# SCHEMATIC.net
KiCad netlist of a schematic drawn in Altium Designer
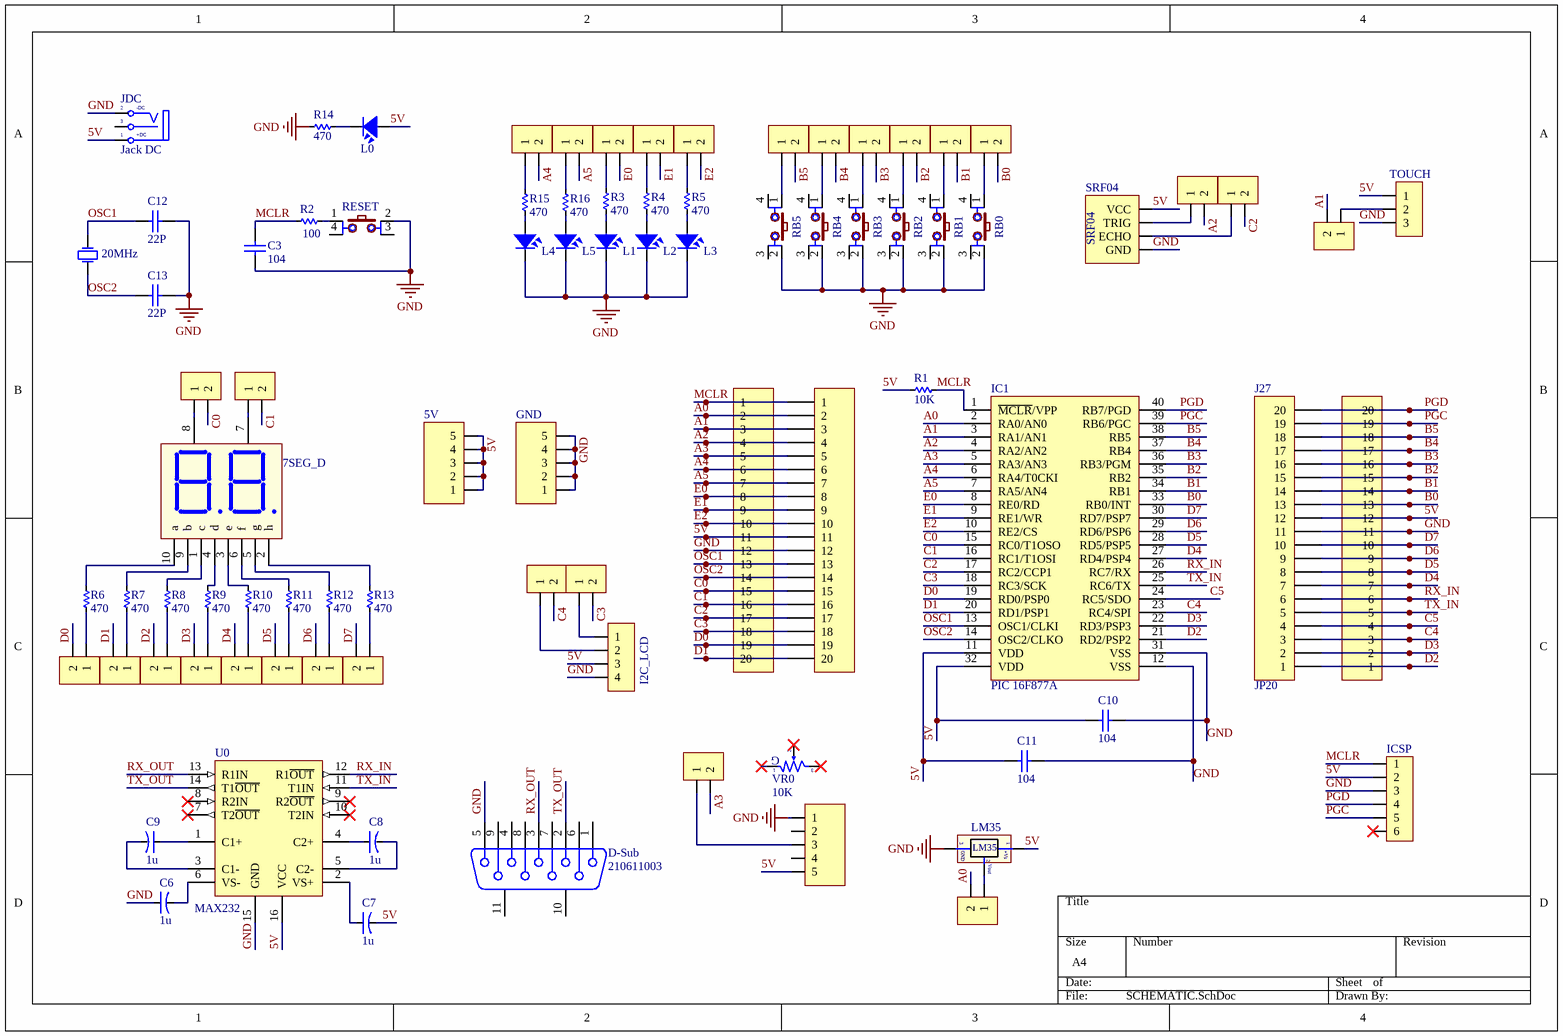
[diagram p0: SCHEMATIC.SchDoc]

(export (version "E")
  (design (tool "Eeschema 10.0.6"))
  (components
    (comp (ref "5V")
      (value "JP5")
      (footprint "JP5-C1T")
      (description "WR-PHD 2.54 mm Angled Socket Header")
      (fields
        (field (name "MANUFACTURER") "Würth Elektronik eiSos GmbH")
        (field (name "PARTNO") "613005143121")
        (field (name "CREATED BY") "Karrer Zheng")
      )
      (libsource (lib "") (part "JP5_1"))
    )
    (comp (ref "C3")
      (value "104")
      (footprint "CN1.5")
      (description "Capacitor")
      (fields (field (name "Comment") "Cap Non-Pol"))
      (libsource (lib "TechMT.VN_Lib_Project v1.0") (part "Cap Non-Pol"))
    )
    (comp (ref "C6")
      (value "1u")
      (footprint "CA-ALU-2.54")
      (description "Capacitor (Semiconductor SIM Model)")
      (fields (field (name "PUBLISHER") "Altium Limited"))
      (libsource (lib "THU VIEN DAY DU") (part "CN-ALU-DIP"))
    )
    (comp (ref "C7")
      (value "1u")
      (footprint "CA-ALU-2.54")
      (description "Capacitor (Semiconductor SIM Model)")
      (fields (field (name "PUBLISHER") "Altium Limited"))
      (libsource (lib "THU VIEN DAY DU") (part "CN-ALU-DIP"))
    )
    (comp (ref "C8")
      (value "1u")
      (footprint "CA-ALU-2.54")
      (description "Capacitor (Semiconductor SIM Model)")
      (fields (field (name "PUBLISHER") "Altium Limited"))
      (libsource (lib "THU VIEN DAY DU") (part "CN-ALU-DIP"))
    )
    (comp (ref "C9")
      (value "1u")
      (footprint "CA-ALU-2.54")
      (description "Capacitor (Semiconductor SIM Model)")
      (fields (field (name "PUBLISHER") "Altium Limited"))
      (libsource (lib "THU VIEN DAY DU") (part "CN-ALU-DIP"))
    )
    (comp (ref "C10")
      (value "104")
      (footprint "CN1.5")
      (description "Capacitor")
      (fields (field (name "Comment") "Cap Non-Pol"))
      (libsource (lib "TechMT.VN_Lib_Project v1.0") (part "Cap Non-Pol"))
    )
    (comp (ref "C11")
      (value "104")
      (footprint "CN1.5")
      (description "Capacitor")
      (fields (field (name "Comment") "Cap Non-Pol"))
      (libsource (lib "TechMT.VN_Lib_Project v1.0") (part "Cap Non-Pol"))
    )
    (comp (ref "C12")
      (value "22P")
      (footprint "CN1.5")
      (description "Capacitor")
      (fields (field (name "Comment") "Cap Non-Pol"))
      (libsource (lib "TechMT.VN_Lib_Project v1.0") (part "Cap Non-Pol"))
    )
    (comp (ref "C13")
      (value "22P")
      (footprint "CN1.5")
      (description "Capacitor")
      (fields (field (name "Comment") "Cap Non-Pol"))
      (libsource (lib "TechMT.VN_Lib_Project v1.0") (part "Cap Non-Pol"))
    )
    (comp (ref "D-Sub")
      (value "210611003")
      (footprint "COM9B")
      (description "D-SUB-Filter Connectors WE-DS, Solder Pin Straight")
      (fields
        (field (name "MANUFACTURER") "Würth Elektronik eiSos GmbH")
        (field (name "CREATED BY") "Christin Zierenner")
      )
      (libsource (lib "THU VIEN DAY DU") (part "CON 9BD"))
    )
    (comp (ref "DS0")
      (value "7SEG_D")
      (footprint "7SEG-D")
      (description "Dual 7 Seg Dipslay")
      (libsource (lib "TechMT.VN_Lib_Project v1.0") (part "LED7-D"))
    )
    (comp (ref "GND")
      (value "JP5")
      (footprint "JP5-C1T")
      (description "WR-PHD 2.54 mm Angled Socket Header")
      (fields
        (field (name "MANUFACTURER") "Würth Elektronik eiSos GmbH")
        (field (name "PARTNO") "613005143121")
        (field (name "CREATED BY") "Karrer Zheng")
      )
      (libsource (lib "") (part "JP5_1"))
    )
    (comp (ref "I2C_LCD")
      (value "JP4")
      (footprint "JP4-C1T")
      (description "WR-PHD 2.54 mm Angled Socket Header")
      (fields
        (field (name "MANUFACTURER") "Würth Elektronik eiSos GmbH")
        (field (name "PARTNO") "613004143121")
        (field (name "CREATED BY") "Karrer Zheng")
      )
      (libsource (lib "THU VIEN DAY DU") (part "JP4"))
    )
    (comp (ref "IC1")
      (value "PIC 16F877A")
      (footprint "DIP40_Socket")
      (description "8K FLASH, 368B RAM, 256B EFROM")
      (fields (field (name "COPYRIGHT BY") "VanDungEvn"))
      (libsource (lib "THU VIEN DAY DU") (part "PIC16F877-PU"))
    )
    (comp (ref "ICSP")
      (value "Header6")
      (footprint "Header6")
      (description "Header IDC, 6 x 1 Pin Vertical 2.54mm Pitch (Non-Boxed, Male)")
      (fields
        (field (name "MANUFACTURER") "Würth Elektronik eiSos GmbH")
        (field (name "PARTNO") "613002143121")
        (field (name "CREATED BY") "Karrer Zheng")
      )
      (libsource (lib "THU VIEN DAY DU") (part "Header6"))
    )
    (comp (ref "J0")
      (value "JP20")
      (footprint "JP20-C1T")
      (description "WR-PHD 2.54 mm Angled Socket Header")
      (fields
        (field (name "MANUFACTURER") "Würth Elektronik eiSos GmbH")
        (field (name "PARTNO") "613020143121")
        (field (name "CREATED BY") "Karrer Zheng")
      )
      (libsource (lib "") (part "JP20_1"))
    )
    (comp (ref "J2")
      (value "JP20")
      (footprint "JP20-D1T")
      (description "WR-PHD 2.54 mm Angled Socket Header")
      (fields
        (field (name "MANUFACTURER") "Würth Elektronik eiSos GmbH")
        (field (name "PARTNO") "613020143121")
        (field (name "CREATED BY") "Karrer Zheng")
      )
      (libsource (lib "THU VIEN DAY DU") (part "JP20"))
    )
    (comp (ref "J26")
      (value "JP20")
      (footprint "JP20-C1T")
      (description "WR-PHD 2.54 mm Angled Socket Header")
      (fields
        (field (name "MANUFACTURER") "Würth Elektronik eiSos GmbH")
        (field (name "PARTNO") "613020143121")
        (field (name "CREATED BY") "Karrer Zheng")
      )
      (libsource (lib "THU VIEN DAY DU") (part "JP20"))
    )
    (comp (ref "J27")
      (value "JP20")
      (footprint "JP20-D1T")
      (description "WR-PHD 2.54 mm Angled Socket Header")
      (fields
        (field (name "MANUFACTURER") "Würth Elektronik eiSos GmbH")
        (field (name "PARTNO") "613020143121")
        (field (name "CREATED BY") "Karrer Zheng")
      )
      (libsource (lib "") (part "JP20_1"))
    )
    (comp (ref "J28")
      (value "JP5")
      (footprint "JP5-C1T")
      (description "WR-PHD 2.54 mm Angled Socket Header")
      (fields
        (field (name "MANUFACTURER") "Würth Elektronik eiSos GmbH")
        (field (name "PARTNO") "613005143121")
        (field (name "CREATED BY") "Karrer Zheng")
      )
      (libsource (lib "THU VIEN DAY DU") (part "JP5"))
    )
    (comp (ref "J29")
      (value "JP2")
      (footprint "JP2-D1T")
      (description "WR-PHD 2.54 mm Angled Socket Header")
      (fields
        (field (name "MANUFACTURER") "Würth Elektronik eiSos GmbH")
        (field (name "PARTNO") "613002143121")
        (field (name "CREATED BY") "Karrer Zheng")
      )
      (libsource (lib "") (part "JP2_1"))
    )
    (comp (ref "JDC")
      (value "Jack DC")
      (footprint "DC0")
      (description "Jac DC input")
      (libsource (lib "THU VIEN DAY DU") (part "DCIN"))
    )
    (comp (ref "JP0")
      (value "JP2")
      (footprint "JP2-D1T")
      (description "WR-PHD 2.54 mm Angled Socket Header")
      (fields
        (field (name "MANUFACTURER") "Würth Elektronik eiSos GmbH")
        (field (name "PARTNO") "613002143121")
        (field (name "CREATED BY") "Karrer Zheng")
      )
      (libsource (lib "") (part "JP2_1"))
    )
    (comp (ref "JP1")
      (value "JP2")
      (footprint "JP2-D1T")
      (description "WR-PHD 2.54 mm Angled Socket Header")
      (fields
        (field (name "MANUFACTURER") "Würth Elektronik eiSos GmbH")
        (field (name "PARTNO") "613002143121")
        (field (name "CREATED BY") "Karrer Zheng")
      )
      (libsource (lib "") (part "JP2_1"))
    )
    (comp (ref "JP2")
      (value "JP2")
      (footprint "JP2-D1T")
      (description "WR-PHD 2.54 mm Angled Socket Header")
      (fields
        (field (name "MANUFACTURER") "Würth Elektronik eiSos GmbH")
        (field (name "PARTNO") "613002143121")
        (field (name "CREATED BY") "Karrer Zheng")
      )
      (libsource (lib "") (part "JP2_1"))
    )
    (comp (ref "JP3")
      (value "JP2")
      (footprint "JP2-D1T")
      (description "WR-PHD 2.54 mm Angled Socket Header")
      (fields
        (field (name "MANUFACTURER") "Würth Elektronik eiSos GmbH")
        (field (name "PARTNO") "613002143121")
        (field (name "CREATED BY") "Karrer Zheng")
      )
      (libsource (lib "") (part "JP2_1"))
    )
    (comp (ref "JP4")
      (value "JP2")
      (footprint "JP2-D1T")
      (description "WR-PHD 2.54 mm Angled Socket Header")
      (fields
        (field (name "MANUFACTURER") "Würth Elektronik eiSos GmbH")
        (field (name "PARTNO") "613002143121")
        (field (name "CREATED BY") "Karrer Zheng")
      )
      (libsource (lib "") (part "JP2_1"))
    )
    (comp (ref "JP5")
      (value "JP2")
      (footprint "JP2-D1T")
      (description "WR-PHD 2.54 mm Angled Socket Header")
      (fields
        (field (name "MANUFACTURER") "Würth Elektronik eiSos GmbH")
        (field (name "PARTNO") "613002143121")
        (field (name "CREATED BY") "Karrer Zheng")
      )
      (libsource (lib "") (part "JP2_1"))
    )
    (comp (ref "JP6")
      (value "JP2")
      (footprint "JP2-D1T")
      (description "WR-PHD 2.54 mm Angled Socket Header")
      (fields
        (field (name "MANUFACTURER") "Würth Elektronik eiSos GmbH")
        (field (name "PARTNO") "613002143121")
        (field (name "CREATED BY") "Karrer Zheng")
      )
      (libsource (lib "") (part "JP2_1"))
    )
    (comp (ref "JP7")
      (value "JP2")
      (footprint "JP2-D1T")
      (description "WR-PHD 2.54 mm Angled Socket Header")
      (fields
        (field (name "MANUFACTURER") "Würth Elektronik eiSos GmbH")
        (field (name "PARTNO") "613002143121")
        (field (name "CREATED BY") "Karrer Zheng")
      )
      (libsource (lib "") (part "JP2_1"))
    )
    (comp (ref "JP8")
      (value "JP2")
      (footprint "JP2-D1T")
      (description "WR-PHD 2.54 mm Angled Socket Header")
      (fields
        (field (name "MANUFACTURER") "Würth Elektronik eiSos GmbH")
        (field (name "PARTNO") "613002143121")
        (field (name "CREATED BY") "Karrer Zheng")
      )
      (libsource (lib "") (part "JP2_1"))
    )
    (comp (ref "JP9")
      (value "JP2")
      (footprint "JP2-D1T")
      (description "WR-PHD 2.54 mm Angled Socket Header")
      (fields
        (field (name "MANUFACTURER") "Würth Elektronik eiSos GmbH")
        (field (name "PARTNO") "613002143121")
        (field (name "CREATED BY") "Karrer Zheng")
      )
      (libsource (lib "") (part "JP2_1"))
    )
    (comp (ref "JP10")
      (value "JP2")
      (footprint "JP2-D1T")
      (description "WR-PHD 2.54 mm Angled Socket Header")
      (fields
        (field (name "MANUFACTURER") "Würth Elektronik eiSos GmbH")
        (field (name "PARTNO") "613002143121")
        (field (name "CREATED BY") "Karrer Zheng")
      )
      (libsource (lib "") (part "JP2_1"))
    )
    (comp (ref "JP11")
      (value "JP2")
      (footprint "JP2-D1T")
      (description "WR-PHD 2.54 mm Angled Socket Header")
      (fields
        (field (name "MANUFACTURER") "Würth Elektronik eiSos GmbH")
        (field (name "PARTNO") "613002143121")
        (field (name "CREATED BY") "Karrer Zheng")
      )
      (libsource (lib "THU VIEN DAY DU") (part "JP2"))
    )
    (comp (ref "JP12")
      (value "JP2")
      (footprint "JP2-D1T")
      (description "WR-PHD 2.54 mm Angled Socket Header")
      (fields
        (field (name "MANUFACTURER") "Würth Elektronik eiSos GmbH")
        (field (name "PARTNO") "613002143121")
        (field (name "CREATED BY") "Karrer Zheng")
      )
      (libsource (lib "") (part "JP2_1"))
    )
    (comp (ref "JP13")
      (value "JP2")
      (footprint "JP2-D1T")
      (description "WR-PHD 2.54 mm Angled Socket Header")
      (fields
        (field (name "MANUFACTURER") "Würth Elektronik eiSos GmbH")
        (field (name "PARTNO") "613002143121")
        (field (name "CREATED BY") "Karrer Zheng")
      )
      (libsource (lib "") (part "JP2_1"))
    )
    (comp (ref "JP14")
      (value "JP2")
      (footprint "JP2-D1T")
      (description "WR-PHD 2.54 mm Angled Socket Header")
      (fields
        (field (name "MANUFACTURER") "Würth Elektronik eiSos GmbH")
        (field (name "PARTNO") "613002143121")
        (field (name "CREATED BY") "Karrer Zheng")
      )
      (libsource (lib "THU VIEN DAY DU") (part "JP2"))
    )
    (comp (ref "JP15")
      (value "JP2")
      (footprint "JP2-D1T")
      (description "WR-PHD 2.54 mm Angled Socket Header")
      (fields
        (field (name "MANUFACTURER") "Würth Elektronik eiSos GmbH")
        (field (name "PARTNO") "613002143121")
        (field (name "CREATED BY") "Karrer Zheng")
      )
      (libsource (lib "THU VIEN DAY DU") (part "JP2"))
    )
    (comp (ref "JP16")
      (value "JP2")
      (footprint "JP2-D1T")
      (description "WR-PHD 2.54 mm Angled Socket Header")
      (fields
        (field (name "MANUFACTURER") "Würth Elektronik eiSos GmbH")
        (field (name "PARTNO") "613002143121")
        (field (name "CREATED BY") "Karrer Zheng")
      )
      (libsource (lib "THU VIEN DAY DU") (part "JP2"))
    )
    (comp (ref "JP17")
      (value "JP2")
      (footprint "JP2-D1T")
      (description "WR-PHD 2.54 mm Angled Socket Header")
      (fields
        (field (name "MANUFACTURER") "Würth Elektronik eiSos GmbH")
        (field (name "PARTNO") "613002143121")
        (field (name "CREATED BY") "Karrer Zheng")
      )
      (libsource (lib "THU VIEN DAY DU") (part "JP2"))
    )
    (comp (ref "JP18")
      (value "JP2")
      (footprint "JP2-D1T")
      (description "WR-PHD 2.54 mm Angled Socket Header")
      (fields
        (field (name "MANUFACTURER") "Würth Elektronik eiSos GmbH")
        (field (name "PARTNO") "613002143121")
        (field (name "CREATED BY") "Karrer Zheng")
      )
      (libsource (lib "THU VIEN DAY DU") (part "JP2"))
    )
    (comp (ref "JP19")
      (value "JP2")
      (footprint "JP2-D1T")
      (description "WR-PHD 2.54 mm Angled Socket Header")
      (fields
        (field (name "MANUFACTURER") "Würth Elektronik eiSos GmbH")
        (field (name "PARTNO") "613002143121")
        (field (name "CREATED BY") "Karrer Zheng")
      )
      (libsource (lib "THU VIEN DAY DU") (part "JP2"))
    )
    (comp (ref "JP20")
      (value "JP2")
      (footprint "JP2-D1T")
      (description "WR-PHD 2.54 mm Angled Socket Header")
      (fields
        (field (name "MANUFACTURER") "Würth Elektronik eiSos GmbH")
        (field (name "PARTNO") "613002143121")
        (field (name "CREATED BY") "Karrer Zheng")
      )
      (libsource (lib "THU VIEN DAY DU") (part "JP2"))
    )
    (comp (ref "JP21")
      (value "JP2")
      (footprint "JP2-D1T")
      (description "WR-PHD 2.54 mm Angled Socket Header")
      (fields
        (field (name "MANUFACTURER") "Würth Elektronik eiSos GmbH")
        (field (name "PARTNO") "613002143121")
        (field (name "CREATED BY") "Karrer Zheng")
      )
      (libsource (lib "THU VIEN DAY DU") (part "JP2"))
    )
    (comp (ref "JP22")
      (value "JP2")
      (footprint "JP2-D1T")
      (description "WR-PHD 2.54 mm Angled Socket Header")
      (fields
        (field (name "MANUFACTURER") "Würth Elektronik eiSos GmbH")
        (field (name "PARTNO") "613002143121")
        (field (name "CREATED BY") "Karrer Zheng")
      )
      (libsource (lib "") (part "JP2_1"))
    )
    (comp (ref "JP23")
      (value "JP2")
      (footprint "JP2-D1T")
      (description "WR-PHD 2.54 mm Angled Socket Header")
      (fields
        (field (name "MANUFACTURER") "Würth Elektronik eiSos GmbH")
        (field (name "PARTNO") "613002143121")
        (field (name "CREATED BY") "Karrer Zheng")
      )
      (libsource (lib "") (part "JP2_1"))
    )
    (comp (ref "JP25")
      (value "JP2")
      (footprint "JP2-D1T")
      (description "WR-PHD 2.54 mm Angled Socket Header")
      (fields
        (field (name "MANUFACTURER") "Würth Elektronik eiSos GmbH")
        (field (name "PARTNO") "613002143121")
        (field (name "CREATED BY") "Karrer Zheng")
      )
      (libsource (lib "THU VIEN DAY DU") (part "JP2"))
    )
    (comp (ref "JP26")
      (value "JP2")
      (footprint "JP2-D1T")
      (description "WR-PHD 2.54 mm Angled Socket Header")
      (fields
        (field (name "MANUFACTURER") "Würth Elektronik eiSos GmbH")
        (field (name "PARTNO") "613002143121")
        (field (name "CREATED BY") "Karrer Zheng")
      )
      (libsource (lib "") (part "JP2_1"))
    )
    (comp (ref "JP27")
      (value "JP2")
      (footprint "JP2-D1T")
      (description "WR-PHD 2.54 mm Angled Socket Header")
      (fields
        (field (name "MANUFACTURER") "Würth Elektronik eiSos GmbH")
        (field (name "PARTNO") "613002143121")
        (field (name "CREATED BY") "Karrer Zheng")
      )
      (libsource (lib "") (part "JP2_1"))
    )
    (comp (ref "L0")
      (value "LED")
      (footprint "LED-5-RED")
      (description "LED Single colour Green and Red")
      (libsource (lib "THU VIEN DAY DU") (part "LED"))
    )
    (comp (ref "L1")
      (value "LED")
      (footprint "LED-5-RED")
      (description "LED Single colour Green and Red")
      (libsource (lib "THU VIEN DAY DU") (part "LED"))
    )
    (comp (ref "L2")
      (value "LED")
      (footprint "LED-5-RED")
      (description "LED Single colour Green and Red")
      (libsource (lib "THU VIEN DAY DU") (part "LED"))
    )
    (comp (ref "L3")
      (value "LED")
      (footprint "LED-5-RED")
      (description "LED Single colour Green and Red")
      (libsource (lib "THU VIEN DAY DU") (part "LED"))
    )
    (comp (ref "L4")
      (value "LED")
      (footprint "LED-5-RED")
      (description "LED Single colour Green and Red")
      (libsource (lib "THU VIEN DAY DU") (part "LED"))
    )
    (comp (ref "L5")
      (value "LED")
      (footprint "LED-5-RED")
      (description "LED Single colour Green and Red")
      (libsource (lib "THU VIEN DAY DU") (part "LED"))
    )
    (comp (ref "LM35")
      (value "LM35")
      (footprint "TO92-123")
      (description "Teminal")
      (libsource (lib "THU VIEN DAY DU") (part "LM35"))
    )
    (comp (ref "R1")
      (value "10K")
      (footprint "RES-1/4W-SMALL")
      (description "Res")
      (fields
        (field (name "MANUFACTURER") "Generic Components")
        (field (name "PUBLISHER") "Altium Hobart Technology Centre")
      )
      (libsource (lib "THU VIEN DAY DU") (part "Res"))
    )
    (comp (ref "R2")
      (value "100")
      (footprint "RES-1/4W-SMALL")
      (description "Res")
      (fields
        (field (name "MANUFACTURER") "Generic Components")
        (field (name "PUBLISHER") "Altium Hobart Technology Centre")
      )
      (libsource (lib "THU VIEN DAY DU") (part "Res"))
    )
    (comp (ref "R3")
      (value "470")
      (footprint "RES-1/4W-SMALL")
      (description "Res")
      (fields
        (field (name "MANUFACTURER") "Generic Components")
        (field (name "PUBLISHER") "Altium Hobart Technology Centre")
      )
      (libsource (lib "THU VIEN DAY DU") (part "Res"))
    )
    (comp (ref "R4")
      (value "470")
      (footprint "RES-1/4W-SMALL")
      (description "Res")
      (fields
        (field (name "MANUFACTURER") "Generic Components")
        (field (name "PUBLISHER") "Altium Hobart Technology Centre")
      )
      (libsource (lib "THU VIEN DAY DU") (part "Res"))
    )
    (comp (ref "R5")
      (value "470")
      (footprint "RES-1/4W-SMALL")
      (description "Res")
      (fields
        (field (name "MANUFACTURER") "Generic Components")
        (field (name "PUBLISHER") "Altium Hobart Technology Centre")
      )
      (libsource (lib "THU VIEN DAY DU") (part "Res"))
    )
    (comp (ref "R6")
      (value "470")
      (footprint "RES-1/4W-SMALL")
      (description "Res")
      (fields
        (field (name "MANUFACTURER") "Generic Components")
        (field (name "PUBLISHER") "Altium Hobart Technology Centre")
      )
      (libsource (lib "THU VIEN DAY DU") (part "Res"))
    )
    (comp (ref "R7")
      (value "470")
      (footprint "RES-1/4W-SMALL")
      (description "Res")
      (fields
        (field (name "MANUFACTURER") "Generic Components")
        (field (name "PUBLISHER") "Altium Hobart Technology Centre")
      )
      (libsource (lib "THU VIEN DAY DU") (part "Res"))
    )
    (comp (ref "R8")
      (value "470")
      (footprint "RES-1/4W-SMALL")
      (description "Res")
      (fields
        (field (name "MANUFACTURER") "Generic Components")
        (field (name "PUBLISHER") "Altium Hobart Technology Centre")
      )
      (libsource (lib "THU VIEN DAY DU") (part "Res"))
    )
    (comp (ref "R9")
      (value "470")
      (footprint "RES-1/4W-SMALL")
      (description "Res")
      (fields
        (field (name "MANUFACTURER") "Generic Components")
        (field (name "PUBLISHER") "Altium Hobart Technology Centre")
      )
      (libsource (lib "THU VIEN DAY DU") (part "Res"))
    )
    (comp (ref "R10")
      (value "470")
      (footprint "RES-1/4W-SMALL")
      (description "Res")
      (fields
        (field (name "MANUFACTURER") "Generic Components")
        (field (name "PUBLISHER") "Altium Hobart Technology Centre")
      )
      (libsource (lib "THU VIEN DAY DU") (part "Res"))
    )
    (comp (ref "R11")
      (value "470")
      (footprint "RES-1/4W-SMALL")
      (description "Res")
      (fields
        (field (name "MANUFACTURER") "Generic Components")
        (field (name "PUBLISHER") "Altium Hobart Technology Centre")
      )
      (libsource (lib "THU VIEN DAY DU") (part "Res"))
    )
    (comp (ref "R12")
      (value "470")
      (footprint "RES-1/4W-SMALL")
      (description "Res")
      (fields
        (field (name "MANUFACTURER") "Generic Components")
        (field (name "PUBLISHER") "Altium Hobart Technology Centre")
      )
      (libsource (lib "THU VIEN DAY DU") (part "Res"))
    )
    (comp (ref "R13")
      (value "470")
      (footprint "RES-1/4W-SMALL")
      (description "Res")
      (fields
        (field (name "MANUFACTURER") "Generic Components")
        (field (name "PUBLISHER") "Altium Hobart Technology Centre")
      )
      (libsource (lib "THU VIEN DAY DU") (part "Res"))
    )
    (comp (ref "R14")
      (value "470")
      (footprint "RES-1/4W-SMALL")
      (description "Res")
      (fields
        (field (name "MANUFACTURER") "Generic Components")
        (field (name "PUBLISHER") "Altium Hobart Technology Centre")
      )
      (libsource (lib "THU VIEN DAY DU") (part "Res"))
    )
    (comp (ref "R15")
      (value "470")
      (footprint "RES-1/4W-SMALL")
      (description "Res")
      (fields
        (field (name "MANUFACTURER") "Generic Components")
        (field (name "PUBLISHER") "Altium Hobart Technology Centre")
      )
      (libsource (lib "THU VIEN DAY DU") (part "Res"))
    )
    (comp (ref "R16")
      (value "470")
      (footprint "RES-1/4W-SMALL")
      (description "Res")
      (fields
        (field (name "MANUFACTURER") "Generic Components")
        (field (name "PUBLISHER") "Altium Hobart Technology Centre")
      )
      (libsource (lib "THU VIEN DAY DU") (part "Res"))
    )
    (comp (ref "RB0")
      (value "~")
      (footprint "SW2-DIP")
      (description "Switch button 4 pin")
      (libsource (lib "THU VIEN DAY DU") (part "SW4"))
    )
    (comp (ref "RB1")
      (value "~")
      (footprint "SW2-DIP")
      (description "Switch button 4 pin")
      (libsource (lib "THU VIEN DAY DU") (part "SW4"))
    )
    (comp (ref "RB2")
      (value "~")
      (footprint "SW2-DIP")
      (description "Switch button 4 pin")
      (libsource (lib "THU VIEN DAY DU") (part "SW4"))
    )
    (comp (ref "RB3")
      (value "~")
      (footprint "SW2-DIP")
      (description "Switch button 4 pin")
      (libsource (lib "THU VIEN DAY DU") (part "SW4"))
    )
    (comp (ref "RB4")
      (value "~")
      (footprint "SW2-DIP")
      (description "Switch button 4 pin")
      (libsource (lib "THU VIEN DAY DU") (part "SW4"))
    )
    (comp (ref "RB5")
      (value "~")
      (footprint "SW2-DIP")
      (description "Switch button 4 pin")
      (libsource (lib "THU VIEN DAY DU") (part "SW4"))
    )
    (comp (ref "RESET")
      (value "~")
      (footprint "SW2-DIP")
      (description "Switch button 4 pin")
      (libsource (lib "THU VIEN DAY DU") (part "SW4"))
    )
    (comp (ref "SRF04")
      (value "SRF04")
      (footprint "SRF04")
      (fields
        (field (name "MANUFACTURER") "Würth Elektronik eiSos GmbH")
        (field (name "PARTNO") "613004143121")
        (field (name "CREATED BY") "Karrer Zheng")
      )
      (libsource (lib "THU VIEN DAY DU") (part "SRF04"))
    )
    (comp (ref "TOUCH")
      (value "JP3")
      (footprint "JP3-C1T")
      (description "WR-PHD 2.54 mm Angled Socket Header")
      (fields
        (field (name "MANUFACTURER") "Würth Elektronik eiSos GmbH")
        (field (name "PARTNO") "613003143121")
        (field (name "CREATED BY") "Karrer Zheng")
      )
      (libsource (lib "THU VIEN DAY DU") (part "JP3"))
    )
    (comp (ref "U0")
      (value "MAX232")
      (footprint "DIP16")
      (description "RS232 LEVEL SHIFTER")
      (fields
        (field (name "MANUFACTURER PART NUMBER") "MAX232DR")
        (field (name "MANUFACTURER") "Texas Instruments")
      )
      (libsource (lib "THU VIEN DAY DU") (part "MAX232"))
    )
    (comp (ref "VR0")
      (value "10K")
      (footprint "VR-S1")
      (description "Var Resistor")
      (libsource (lib "THU VIEN DAY DU") (part "VR-S"))
    )
    (comp (ref "Y1")
      (value "20MHz")
      (footprint "xtal")
      (description "Crystal Oscillator")
      (fields (field (name "PUBLISHER") "Altium Limited"))
      (libsource (lib "TechMT.VN_Lib_Project v1.0") (part "Crystal"))
    )
  )
  (nets
    (net (code "1") (name "/5V") (class "Default")
      (node (ref "5V") (pin "1") (pinfunction "1_1") (pintype "passive"))
      (node (ref "5V") (pin "2") (pinfunction "2_2") (pintype "passive"))
      (node (ref "5V") (pin "3") (pinfunction "3_3") (pintype "passive"))
      (node (ref "5V") (pin "4") (pinfunction "4_4") (pintype "passive"))
      (node (ref "5V") (pin "5") (pinfunction "5_5") (pintype "passive"))
      (node (ref "C10") (pin "1") (pinfunction "1_1") (pintype "passive"))
      (node (ref "C11") (pin "1") (pinfunction "1_1") (pintype "passive"))
      (node (ref "C7") (pin "2") (pinfunction "2_2") (pintype "passive"))
      (node (ref "I2C_LCD") (pin "3") (pinfunction "3_3") (pintype "passive"))
      (node (ref "IC1") (pin "11") (pinfunction "VDD_11") (pintype "passive"))
      (node (ref "IC1") (pin "32") (pinfunction "VDD_32") (pintype "passive"))
      (node (ref "ICSP") (pin "2") (pinfunction "2_2") (pintype "passive"))
      (node (ref "J0") (pin "12") (pinfunction "12_12") (pintype "passive"))
      (node (ref "J2") (pin "11") (pinfunction "11_11") (pintype "passive"))
      (node (ref "J26") (pin "11") (pinfunction "11_11") (pintype "passive"))
      (node (ref "J27") (pin "12") (pinfunction "12_12") (pintype "passive"))
      (node (ref "J28") (pin "5") (pinfunction "5_5") (pintype "passive"))
      (node (ref "JDC") (pin "1") (pinfunction "T_1") (pintype "passive"))
      (node (ref "L0") (pin "1") (pinfunction "1_1") (pintype "passive"))
      (node (ref "LM35") (pin "1") (pinfunction "+Vs_1") (pintype "passive"))
      (node (ref "R1") (pin "2") (pinfunction "2_2") (pintype "passive"))
      (node (ref "SRF04") (pin "4") (pinfunction "VCC_4") (pintype "passive"))
      (node (ref "TOUCH") (pin "1") (pinfunction "1_1") (pintype "passive"))
      (node (ref "U0") (pin "16") (pinfunction "VCC_16") (pintype "power_in"))
    )
    (net (code "2") (name "/A0") (class "Default")
      (node (ref "IC1") (pin "2") (pinfunction "RA0/AN0_2") (pintype "passive"))
      (node (ref "J2") (pin "2") (pinfunction "2_2") (pintype "passive"))
      (node (ref "J26") (pin "2") (pinfunction "2_2") (pintype "passive"))
      (node (ref "JP25") (pin "2") (pinfunction "2_2") (pintype "passive"))
    )
    (net (code "3") (name "/A1") (class "Default")
      (node (ref "IC1") (pin "3") (pinfunction "RA1/AN1_3") (pintype "passive"))
      (node (ref "J2") (pin "3") (pinfunction "3_3") (pintype "passive"))
      (node (ref "J26") (pin "3") (pinfunction "3_3") (pintype "passive"))
      (node (ref "JP11") (pin "2") (pinfunction "2_2") (pintype "passive"))
    )
    (net (code "4") (name "/A2") (class "Default")
      (node (ref "IC1") (pin "4") (pinfunction "RA2/AN2_4") (pintype "passive"))
      (node (ref "J2") (pin "4") (pinfunction "4_4") (pintype "passive"))
      (node (ref "J26") (pin "4") (pinfunction "4_4") (pintype "passive"))
      (node (ref "JP9") (pin "2") (pinfunction "2_2") (pintype "passive"))
    )
    (net (code "5") (name "/A3") (class "Default")
      (node (ref "IC1") (pin "5") (pinfunction "RA3/AN3_5") (pintype "passive"))
      (node (ref "J2") (pin "5") (pinfunction "5_5") (pintype "passive"))
      (node (ref "J26") (pin "5") (pinfunction "5_5") (pintype "passive"))
      (node (ref "J29") (pin "2") (pinfunction "2_2") (pintype "passive"))
    )
    (net (code "6") (name "/A4") (class "Default")
      (node (ref "IC1") (pin "6") (pinfunction "RA4/T0CKI_6") (pintype "passive"))
      (node (ref "J2") (pin "6") (pinfunction "6_6") (pintype "passive"))
      (node (ref "J26") (pin "6") (pinfunction "6_6") (pintype "passive"))
      (node (ref "JP26") (pin "2") (pinfunction "2_2") (pintype "passive"))
    )
    (net (code "7") (name "/A5") (class "Default")
      (node (ref "IC1") (pin "7") (pinfunction "RA5/AN4_7") (pintype "passive"))
      (node (ref "J2") (pin "7") (pinfunction "7_7") (pintype "passive"))
      (node (ref "J26") (pin "7") (pinfunction "7_7") (pintype "passive"))
      (node (ref "JP27") (pin "2") (pinfunction "2_2") (pintype "passive"))
    )
    (net (code "8") (name "/B0") (class "Default")
      (node (ref "IC1") (pin "33") (pinfunction "RB0/INT_33") (pintype "passive"))
      (node (ref "J0") (pin "13") (pinfunction "13_13") (pintype "passive"))
      (node (ref "J27") (pin "13") (pinfunction "13_13") (pintype "passive"))
      (node (ref "JP3") (pin "2") (pinfunction "2_2") (pintype "passive"))
    )
    (net (code "9") (name "/B1") (class "Default")
      (node (ref "IC1") (pin "34") (pinfunction "RB1_34") (pintype "passive"))
      (node (ref "J0") (pin "14") (pinfunction "14_14") (pintype "passive"))
      (node (ref "J27") (pin "14") (pinfunction "14_14") (pintype "passive"))
      (node (ref "JP4") (pin "2") (pinfunction "2_2") (pintype "passive"))
    )
    (net (code "10") (name "/B2") (class "Default")
      (node (ref "IC1") (pin "35") (pinfunction "RB2_35") (pintype "passive"))
      (node (ref "J0") (pin "15") (pinfunction "15_15") (pintype "passive"))
      (node (ref "J27") (pin "15") (pinfunction "15_15") (pintype "passive"))
      (node (ref "JP5") (pin "2") (pinfunction "2_2") (pintype "passive"))
    )
    (net (code "11") (name "/B3") (class "Default")
      (node (ref "IC1") (pin "36") (pinfunction "RB3/PGM_36") (pintype "passive"))
      (node (ref "J0") (pin "16") (pinfunction "16_16") (pintype "passive"))
      (node (ref "J27") (pin "16") (pinfunction "16_16") (pintype "passive"))
      (node (ref "JP6") (pin "2") (pinfunction "2_2") (pintype "passive"))
    )
    (net (code "12") (name "/B4") (class "Default")
      (node (ref "IC1") (pin "37") (pinfunction "RB4_37") (pintype "passive"))
      (node (ref "J0") (pin "17") (pinfunction "17_17") (pintype "passive"))
      (node (ref "J27") (pin "17") (pinfunction "17_17") (pintype "passive"))
      (node (ref "JP7") (pin "2") (pinfunction "2_2") (pintype "passive"))
    )
    (net (code "13") (name "/B5") (class "Default")
      (node (ref "IC1") (pin "38") (pinfunction "RB5_38") (pintype "passive"))
      (node (ref "J0") (pin "18") (pinfunction "18_18") (pintype "passive"))
      (node (ref "J27") (pin "18") (pinfunction "18_18") (pintype "passive"))
      (node (ref "JP8") (pin "2") (pinfunction "2_2") (pintype "passive"))
    )
    (net (code "14") (name "/C0") (class "Default")
      (node (ref "IC1") (pin "15") (pinfunction "RC0/T1OSO_15") (pintype "passive"))
      (node (ref "J2") (pin "15") (pinfunction "15_15") (pintype "passive"))
      (node (ref "J26") (pin "15") (pinfunction "15_15") (pintype "passive"))
      (node (ref "JP12") (pin "2") (pinfunction "2_2") (pintype "passive"))
    )
    (net (code "15") (name "/C1") (class "Default")
      (node (ref "IC1") (pin "16") (pinfunction "RC1/T1OSI_16") (pintype "passive"))
      (node (ref "J2") (pin "16") (pinfunction "16_16") (pintype "passive"))
      (node (ref "J26") (pin "16") (pinfunction "16_16") (pintype "passive"))
      (node (ref "JP13") (pin "2") (pinfunction "2_2") (pintype "passive"))
    )
    (net (code "16") (name "/C2") (class "Default")
      (node (ref "IC1") (pin "17") (pinfunction "RC2/CCP1_17") (pintype "passive"))
      (node (ref "J2") (pin "17") (pinfunction "17_17") (pintype "passive"))
      (node (ref "J26") (pin "17") (pinfunction "17_17") (pintype "passive"))
      (node (ref "JP10") (pin "2") (pinfunction "2_2") (pintype "passive"))
    )
    (net (code "17") (name "/C3") (class "Default")
      (node (ref "IC1") (pin "18") (pinfunction "RC3/SCK_18") (pintype "passive"))
      (node (ref "J2") (pin "18") (pinfunction "18_18") (pintype "passive"))
      (node (ref "J26") (pin "18") (pinfunction "18_18") (pintype "passive"))
      (node (ref "JP23") (pin "2") (pinfunction "2_2") (pintype "passive"))
    )
    (net (code "18") (name "/C4") (class "Default")
      (node (ref "IC1") (pin "23") (pinfunction "RC4/SPI_23") (pintype "passive"))
      (node (ref "J0") (pin "3") (pinfunction "3_3") (pintype "passive"))
      (node (ref "J27") (pin "3") (pinfunction "3_3") (pintype "passive"))
      (node (ref "JP22") (pin "2") (pinfunction "2_2") (pintype "passive"))
    )
    (net (code "19") (name "/C5") (class "Default")
      (node (ref "IC1") (pin "24") (pinfunction "RC5/SDO_24") (pintype "passive"))
      (node (ref "J0") (pin "4") (pinfunction "4_4") (pintype "passive"))
      (node (ref "J27") (pin "4") (pinfunction "4_4") (pintype "passive"))
    )
    (net (code "20") (name "/D0") (class "Default")
      (node (ref "IC1") (pin "19") (pinfunction "RD0/PSP0_19") (pintype "passive"))
      (node (ref "J2") (pin "19") (pinfunction "19_19") (pintype "passive"))
      (node (ref "J26") (pin "19") (pinfunction "19_19") (pintype "passive"))
      (node (ref "JP14") (pin "2") (pinfunction "2_2") (pintype "passive"))
    )
    (net (code "21") (name "/D1") (class "Default")
      (node (ref "IC1") (pin "20") (pinfunction "RD1/PSP1_20") (pintype "passive"))
      (node (ref "J2") (pin "20") (pinfunction "20_20") (pintype "passive"))
      (node (ref "J26") (pin "20") (pinfunction "20_20") (pintype "passive"))
      (node (ref "JP15") (pin "2") (pinfunction "2_2") (pintype "passive"))
    )
    (net (code "22") (name "/D2") (class "Default")
      (node (ref "IC1") (pin "21") (pinfunction "RD2/PSP2_21") (pintype "passive"))
      (node (ref "J0") (pin "1") (pinfunction "1_1") (pintype "passive"))
      (node (ref "J27") (pin "1") (pinfunction "1_1") (pintype "passive"))
      (node (ref "JP16") (pin "2") (pinfunction "2_2") (pintype "passive"))
    )
    (net (code "23") (name "/D3") (class "Default")
      (node (ref "IC1") (pin "22") (pinfunction "RD3/PSP3_22") (pintype "passive"))
      (node (ref "J0") (pin "2") (pinfunction "2_2") (pintype "passive"))
      (node (ref "J27") (pin "2") (pinfunction "2_2") (pintype "passive"))
      (node (ref "JP17") (pin "2") (pinfunction "2_2") (pintype "passive"))
    )
    (net (code "24") (name "/D4") (class "Default")
      (node (ref "IC1") (pin "27") (pinfunction "RD4/PSP4_27") (pintype "passive"))
      (node (ref "J0") (pin "7") (pinfunction "7_7") (pintype "passive"))
      (node (ref "J27") (pin "7") (pinfunction "7_7") (pintype "passive"))
      (node (ref "JP18") (pin "2") (pinfunction "2_2") (pintype "passive"))
    )
    (net (code "25") (name "/D5") (class "Default")
      (node (ref "IC1") (pin "28") (pinfunction "RD5/PSP5_28") (pintype "passive"))
      (node (ref "J0") (pin "8") (pinfunction "8_8") (pintype "passive"))
      (node (ref "J27") (pin "8") (pinfunction "8_8") (pintype "passive"))
      (node (ref "JP19") (pin "2") (pinfunction "2_2") (pintype "passive"))
    )
    (net (code "26") (name "/D6") (class "Default")
      (node (ref "IC1") (pin "29") (pinfunction "RD6/PSP6_29") (pintype "passive"))
      (node (ref "J0") (pin "9") (pinfunction "9_9") (pintype "passive"))
      (node (ref "J27") (pin "9") (pinfunction "9_9") (pintype "passive"))
      (node (ref "JP20") (pin "2") (pinfunction "2_2") (pintype "passive"))
    )
    (net (code "27") (name "/D7") (class "Default")
      (node (ref "IC1") (pin "30") (pinfunction "RD7/PSP7_30") (pintype "passive"))
      (node (ref "J0") (pin "10") (pinfunction "10_10") (pintype "passive"))
      (node (ref "J27") (pin "10") (pinfunction "10_10") (pintype "passive"))
      (node (ref "JP21") (pin "2") (pinfunction "2_2") (pintype "passive"))
    )
    (net (code "28") (name "/E0") (class "Default")
      (node (ref "IC1") (pin "8") (pinfunction "RE0/RD_8") (pintype "passive"))
      (node (ref "J2") (pin "8") (pinfunction "8_8") (pintype "passive"))
      (node (ref "J26") (pin "8") (pinfunction "8_8") (pintype "passive"))
      (node (ref "JP0") (pin "2") (pinfunction "2_2") (pintype "passive"))
    )
    (net (code "29") (name "/E1") (class "Default")
      (node (ref "IC1") (pin "9") (pinfunction "RE1/WR_9") (pintype "passive"))
      (node (ref "J2") (pin "9") (pinfunction "9_9") (pintype "passive"))
      (node (ref "J26") (pin "9") (pinfunction "9_9") (pintype "passive"))
      (node (ref "JP1") (pin "2") (pinfunction "2_2") (pintype "passive"))
    )
    (net (code "30") (name "/E2") (class "Default")
      (node (ref "IC1") (pin "10") (pinfunction "RE2/CS_10") (pintype "passive"))
      (node (ref "J2") (pin "10") (pinfunction "10_10") (pintype "passive"))
      (node (ref "J26") (pin "10") (pinfunction "10_10") (pintype "passive"))
      (node (ref "JP2") (pin "2") (pinfunction "2_2") (pintype "passive"))
    )
    (net (code "31") (name "/MCLR") (class "Default")
      (node (ref "C3") (pin "1") (pinfunction "1_1") (pintype "passive"))
      (node (ref "IC1") (pin "1") (pinfunction "~{MCLR}/VPP_1") (pintype "passive"))
      (node (ref "ICSP") (pin "1") (pinfunction "1_1") (pintype "passive"))
      (node (ref "J2") (pin "1") (pinfunction "1_1") (pintype "passive"))
      (node (ref "J26") (pin "1") (pinfunction "1_1") (pintype "passive"))
      (node (ref "R1") (pin "1") (pinfunction "1_1") (pintype "passive"))
      (node (ref "R2") (pin "2") (pinfunction "2_2") (pintype "passive"))
    )
    (net (code "32") (name "/OSC1") (class "Default")
      (node (ref "C12") (pin "1") (pinfunction "1_1") (pintype "passive"))
      (node (ref "IC1") (pin "13") (pinfunction "OSC1/CLKI_13") (pintype "passive"))
      (node (ref "J2") (pin "13") (pinfunction "13_13") (pintype "passive"))
      (node (ref "J26") (pin "13") (pinfunction "13_13") (pintype "passive"))
      (node (ref "Y1") (pin "2") (pinfunction "OSC2_2") (pintype "passive"))
    )
    (net (code "33") (name "/OSC2") (class "Default")
      (node (ref "C13") (pin "1") (pinfunction "1_1") (pintype "passive"))
      (node (ref "IC1") (pin "14") (pinfunction "OSC2/CLKO_14") (pintype "passive"))
      (node (ref "J2") (pin "14") (pinfunction "14_14") (pintype "passive"))
      (node (ref "J26") (pin "14") (pinfunction "14_14") (pintype "passive"))
      (node (ref "Y1") (pin "1") (pinfunction "OSC1_1") (pintype "passive"))
    )
    (net (code "34") (name "/PGC") (class "Default")
      (node (ref "IC1") (pin "39") (pinfunction "RB6/PGC_39") (pintype "passive"))
      (node (ref "ICSP") (pin "5") (pinfunction "5_5") (pintype "passive"))
      (node (ref "J0") (pin "19") (pinfunction "19_19") (pintype "passive"))
      (node (ref "J27") (pin "19") (pinfunction "19_19") (pintype "passive"))
    )
    (net (code "35") (name "/PGD") (class "Default")
      (node (ref "IC1") (pin "40") (pinfunction "RB7/PGD_40") (pintype "passive"))
      (node (ref "ICSP") (pin "4") (pinfunction "4_4") (pintype "passive"))
      (node (ref "J0") (pin "20") (pinfunction "20_20") (pintype "passive"))
      (node (ref "J27") (pin "20") (pinfunction "20_20") (pintype "passive"))
    )
    (net (code "36") (name "/RX_IN") (class "Default")
      (node (ref "IC1") (pin "26") (pinfunction "RC7/RX_26") (pintype "passive"))
      (node (ref "J0") (pin "6") (pinfunction "6_6") (pintype "passive"))
      (node (ref "J27") (pin "6") (pinfunction "6_6") (pintype "passive"))
      (node (ref "U0") (pin "12") (pinfunction "R1~{OUT}_12") (pintype "output"))
    )
    (net (code "37") (name "/RX_OUT") (class "Default")
      (node (ref "D-Sub") (pin "3") (pinfunction "3_3") (pintype "passive"))
      (node (ref "U0") (pin "13") (pinfunction "R1IN_13") (pintype "input"))
    )
    (net (code "38") (name "/TX_IN") (class "Default")
      (node (ref "IC1") (pin "25") (pinfunction "RC6/TX_25") (pintype "passive"))
      (node (ref "J0") (pin "5") (pinfunction "5_5") (pintype "passive"))
      (node (ref "J27") (pin "5") (pinfunction "5_5") (pintype "passive"))
      (node (ref "U0") (pin "11") (pinfunction "T1IN_11") (pintype "input"))
    )
    (net (code "39") (name "/TX_OUT") (class "Default")
      (node (ref "D-Sub") (pin "2") (pinfunction "2_2") (pintype "passive"))
      (node (ref "U0") (pin "14") (pinfunction "T1~{OUT}_14") (pintype "output"))
    )
    (net (code "40") (name "GND") (class "Default")
      (node (ref "C10") (pin "2") (pinfunction "2_2") (pintype "passive"))
      (node (ref "C11") (pin "2") (pinfunction "2_2") (pintype "passive"))
      (node (ref "C12") (pin "2") (pinfunction "2_2") (pintype "passive"))
      (node (ref "C13") (pin "2") (pinfunction "2_2") (pintype "passive"))
      (node (ref "C3") (pin "2") (pinfunction "2_2") (pintype "passive"))
      (node (ref "C6") (pin "1") (pinfunction "1_1") (pintype "passive"))
      (node (ref "D-Sub") (pin "5") (pinfunction "5_5") (pintype "passive"))
      (node (ref "GND") (pin "1") (pinfunction "1_1") (pintype "passive"))
      (node (ref "GND") (pin "2") (pinfunction "2_2") (pintype "passive"))
      (node (ref "GND") (pin "3") (pinfunction "3_3") (pintype "passive"))
      (node (ref "GND") (pin "4") (pinfunction "4_4") (pintype "passive"))
      (node (ref "GND") (pin "5") (pinfunction "5_5") (pintype "passive"))
      (node (ref "I2C_LCD") (pin "4") (pinfunction "4_4") (pintype "passive"))
      (node (ref "IC1") (pin "12") (pinfunction "VSS_12") (pintype "passive"))
      (node (ref "IC1") (pin "31") (pinfunction "VSS_31") (pintype "passive"))
      (node (ref "ICSP") (pin "3") (pinfunction "3_3") (pintype "passive"))
      (node (ref "J0") (pin "11") (pinfunction "11_11") (pintype "passive"))
      (node (ref "J2") (pin "12") (pinfunction "12_12") (pintype "passive"))
      (node (ref "J26") (pin "12") (pinfunction "12_12") (pintype "passive"))
      (node (ref "J27") (pin "11") (pinfunction "11_11") (pintype "passive"))
      (node (ref "J28") (pin "1") (pinfunction "1_1") (pintype "passive"))
      (node (ref "JDC") (pin "2") (pinfunction "TN_2") (pintype "passive"))
      (node (ref "L1") (pin "2") (pinfunction "2_2") (pintype "passive"))
      (node (ref "L2") (pin "2") (pinfunction "2_2") (pintype "passive"))
      (node (ref "L3") (pin "2") (pinfunction "2_2") (pintype "passive"))
      (node (ref "L4") (pin "2") (pinfunction "2_2") (pintype "passive"))
      (node (ref "L5") (pin "2") (pinfunction "2_2") (pintype "passive"))
      (node (ref "LM35") (pin "3") (pinfunction "-_3") (pintype "passive"))
      (node (ref "R14") (pin "2") (pinfunction "2_2") (pintype "passive"))
      (node (ref "RB0") (pin "2") (pinfunction "2_2") (pintype "passive"))
      (node (ref "RB1") (pin "2") (pinfunction "2_2") (pintype "passive"))
      (node (ref "RB2") (pin "2") (pinfunction "2_2") (pintype "passive"))
      (node (ref "RB3") (pin "2") (pinfunction "2_2") (pintype "passive"))
      (node (ref "RB4") (pin "2") (pinfunction "2_2") (pintype "passive"))
      (node (ref "RB5") (pin "2") (pinfunction "2_2") (pintype "passive"))
      (node (ref "RESET") (pin "2") (pinfunction "2_2") (pintype "passive"))
      (node (ref "SRF04") (pin "1") (pinfunction "GND_1") (pintype "passive"))
      (node (ref "TOUCH") (pin "3") (pinfunction "3_3") (pintype "passive"))
      (node (ref "U0") (pin "15") (pinfunction "GND_15") (pintype "power_in"))
    )
    (net (code "41") (name "Net-(DS0-L2)") (class "Default")
      (node (ref "DS0") (pin "7") (pinfunction "L2_7") (pintype "passive"))
      (node (ref "JP13") (pin "1") (pinfunction "1_1") (pintype "passive"))
    )
    (net (code "42") (name "Net-(DS0-Vcc)") (class "Default")
      (node (ref "DS0") (pin "8") (pinfunction "Vcc_8") (pintype "passive"))
      (node (ref "JP12") (pin "1") (pinfunction "1_1") (pintype "passive"))
    )
    (net (code "43") (name "Net-(DS0-a)") (class "Default")
      (node (ref "DS0") (pin "10") (pinfunction "a_10") (pintype "passive"))
      (node (ref "R6") (pin "1") (pinfunction "1_1") (pintype "passive"))
    )
    (net (code "44") (name "Net-(DS0-b)") (class "Default")
      (node (ref "DS0") (pin "9") (pinfunction "b_9") (pintype "passive"))
      (node (ref "R7") (pin "1") (pinfunction "1_1") (pintype "passive"))
    )
    (net (code "45") (name "Net-(DS0-c)") (class "Default")
      (node (ref "DS0") (pin "1") (pinfunction "c_1") (pintype "passive"))
      (node (ref "R8") (pin "1") (pinfunction "1_1") (pintype "passive"))
    )
    (net (code "46") (name "Net-(DS0-d)") (class "Default")
      (node (ref "DS0") (pin "4") (pinfunction "d_4") (pintype "passive"))
      (node (ref "R9") (pin "1") (pinfunction "1_1") (pintype "passive"))
    )
    (net (code "47") (name "Net-(DS0-e)") (class "Default")
      (node (ref "DS0") (pin "3") (pinfunction "e_3") (pintype "passive"))
      (node (ref "R10") (pin "1") (pinfunction "1_1") (pintype "passive"))
    )
    (net (code "48") (name "Net-(DS0-f)") (class "Default")
      (node (ref "DS0") (pin "6") (pinfunction "f_6") (pintype "passive"))
      (node (ref "R11") (pin "1") (pinfunction "1_1") (pintype "passive"))
    )
    (net (code "49") (name "Net-(DS0-g)") (class "Default")
      (node (ref "DS0") (pin "5") (pinfunction "g_5") (pintype "passive"))
      (node (ref "R12") (pin "1") (pinfunction "1_1") (pintype "passive"))
    )
    (net (code "50") (name "Net-(DS0-h)") (class "Default")
      (node (ref "DS0") (pin "2") (pinfunction "h_2") (pintype "passive"))
      (node (ref "R13") (pin "1") (pinfunction "1_1") (pintype "passive"))
    )
    (net (code "51") (name "Net-(I2C_LCD-Pad1)") (class "Default")
      (node (ref "I2C_LCD") (pin "1") (pinfunction "1_1") (pintype "passive"))
      (node (ref "JP23") (pin "1") (pinfunction "1_1") (pintype "passive"))
    )
    (net (code "52") (name "Net-(I2C_LCD-Pad2)") (class "Default")
      (node (ref "I2C_LCD") (pin "2") (pinfunction "2_2") (pintype "passive"))
      (node (ref "JP22") (pin "1") (pinfunction "1_1") (pintype "passive"))
    )
    (net (code "53") (name "Net-(J28-Pad3)") (class "Default")
      (node (ref "J28") (pin "3") (pinfunction "3_3") (pintype "passive"))
      (node (ref "J29") (pin "1") (pinfunction "1_1") (pintype "passive"))
    )
    (net (code "54") (name "Net-(JP0-Pad1)") (class "Default")
      (node (ref "JP0") (pin "1") (pinfunction "1_1") (pintype "passive"))
      (node (ref "R3") (pin "1") (pinfunction "1_1") (pintype "passive"))
    )
    (net (code "55") (name "Net-(JP1-Pad1)") (class "Default")
      (node (ref "JP1") (pin "1") (pinfunction "1_1") (pintype "passive"))
      (node (ref "R4") (pin "1") (pinfunction "1_1") (pintype "passive"))
    )
    (net (code "56") (name "Net-(JP2-Pad1)") (class "Default")
      (node (ref "JP2") (pin "1") (pinfunction "1_1") (pintype "passive"))
      (node (ref "R5") (pin "1") (pinfunction "1_1") (pintype "passive"))
    )
    (net (code "57") (name "Net-(JP3-Pad1)") (class "Default")
      (node (ref "JP3") (pin "1") (pinfunction "1_1") (pintype "passive"))
      (node (ref "RB0") (pin "1") (pintype "passive"))
    )
    (net (code "58") (name "Net-(JP4-Pad1)") (class "Default")
      (node (ref "JP4") (pin "1") (pinfunction "1_1") (pintype "passive"))
      (node (ref "RB1") (pin "1") (pintype "passive"))
    )
    (net (code "59") (name "Net-(JP5-Pad1)") (class "Default")
      (node (ref "JP5") (pin "1") (pinfunction "1_1") (pintype "passive"))
      (node (ref "RB2") (pin "1") (pintype "passive"))
    )
    (net (code "60") (name "Net-(JP6-Pad1)") (class "Default")
      (node (ref "JP6") (pin "1") (pinfunction "1_1") (pintype "passive"))
      (node (ref "RB3") (pin "1") (pintype "passive"))
    )
    (net (code "61") (name "Net-(JP7-Pad1)") (class "Default")
      (node (ref "JP7") (pin "1") (pinfunction "1_1") (pintype "passive"))
      (node (ref "RB4") (pin "1") (pintype "passive"))
    )
    (net (code "62") (name "Net-(JP8-Pad1)") (class "Default")
      (node (ref "JP8") (pin "1") (pinfunction "1_1") (pintype "passive"))
      (node (ref "RB5") (pin "1") (pintype "passive"))
    )
    (net (code "63") (name "Net-(JP11-Pad1)") (class "Default")
      (node (ref "JP11") (pin "1") (pinfunction "1_1") (pintype "passive"))
      (node (ref "TOUCH") (pin "2") (pinfunction "2_2") (pintype "passive"))
    )
    (net (code "64") (name "Net-(JP14-Pad1)") (class "Default")
      (node (ref "JP14") (pin "1") (pinfunction "1_1") (pintype "passive"))
      (node (ref "R6") (pin "2") (pinfunction "2_2") (pintype "passive"))
    )
    (net (code "65") (name "Net-(JP15-Pad1)") (class "Default")
      (node (ref "JP15") (pin "1") (pinfunction "1_1") (pintype "passive"))
      (node (ref "R7") (pin "2") (pinfunction "2_2") (pintype "passive"))
    )
    (net (code "66") (name "Net-(JP16-Pad1)") (class "Default")
      (node (ref "JP16") (pin "1") (pinfunction "1_1") (pintype "passive"))
      (node (ref "R8") (pin "2") (pinfunction "2_2") (pintype "passive"))
    )
    (net (code "67") (name "Net-(JP17-Pad1)") (class "Default")
      (node (ref "JP17") (pin "1") (pinfunction "1_1") (pintype "passive"))
      (node (ref "R9") (pin "2") (pinfunction "2_2") (pintype "passive"))
    )
    (net (code "68") (name "Net-(JP18-Pad1)") (class "Default")
      (node (ref "JP18") (pin "1") (pinfunction "1_1") (pintype "passive"))
      (node (ref "R10") (pin "2") (pinfunction "2_2") (pintype "passive"))
    )
    (net (code "69") (name "Net-(JP19-Pad1)") (class "Default")
      (node (ref "JP19") (pin "1") (pinfunction "1_1") (pintype "passive"))
      (node (ref "R11") (pin "2") (pinfunction "2_2") (pintype "passive"))
    )
    (net (code "70") (name "Net-(JP20-Pad1)") (class "Default")
      (node (ref "JP20") (pin "1") (pinfunction "1_1") (pintype "passive"))
      (node (ref "R12") (pin "2") (pinfunction "2_2") (pintype "passive"))
    )
    (net (code "71") (name "Net-(JP21-Pad1)") (class "Default")
      (node (ref "JP21") (pin "1") (pinfunction "1_1") (pintype "passive"))
      (node (ref "R13") (pin "2") (pinfunction "2_2") (pintype "passive"))
    )
    (net (code "72") (name "Net-(JP26-Pad1)") (class "Default")
      (node (ref "JP26") (pin "1") (pinfunction "1_1") (pintype "passive"))
      (node (ref "R15") (pin "1") (pinfunction "1_1") (pintype "passive"))
    )
    (net (code "73") (name "Net-(JP27-Pad1)") (class "Default")
      (node (ref "JP27") (pin "1") (pinfunction "1_1") (pintype "passive"))
      (node (ref "R16") (pin "1") (pinfunction "1_1") (pintype "passive"))
    )
    (net (code "74") (name "Net-(L0-Pad2)") (class "Default")
      (node (ref "L0") (pin "2") (pinfunction "2_2") (pintype "passive"))
      (node (ref "R14") (pin "1") (pinfunction "1_1") (pintype "passive"))
    )
    (net (code "75") (name "Net-(L1-Pad1)") (class "Default")
      (node (ref "L1") (pin "1") (pinfunction "1_1") (pintype "passive"))
      (node (ref "R3") (pin "2") (pinfunction "2_2") (pintype "passive"))
    )
    (net (code "76") (name "Net-(L2-Pad1)") (class "Default")
      (node (ref "L2") (pin "1") (pinfunction "1_1") (pintype "passive"))
      (node (ref "R4") (pin "2") (pinfunction "2_2") (pintype "passive"))
    )
    (net (code "77") (name "Net-(L3-Pad1)") (class "Default")
      (node (ref "L3") (pin "1") (pinfunction "1_1") (pintype "passive"))
      (node (ref "R5") (pin "2") (pinfunction "2_2") (pintype "passive"))
    )
    (net (code "78") (name "Net-(L4-Pad1)") (class "Default")
      (node (ref "L4") (pin "1") (pinfunction "1_1") (pintype "passive"))
      (node (ref "R15") (pin "2") (pinfunction "2_2") (pintype "passive"))
    )
    (net (code "79") (name "Net-(L5-Pad1)") (class "Default")
      (node (ref "L5") (pin "1") (pinfunction "1_1") (pintype "passive"))
      (node (ref "R16") (pin "2") (pinfunction "2_2") (pintype "passive"))
    )
    (net (code "80") (name "Net-(LM35-Vout)") (class "Default")
      (node (ref "JP25") (pin "1") (pinfunction "1_1") (pintype "passive"))
      (node (ref "LM35") (pin "2") (pinfunction "Vout_2") (pintype "passive"))
    )
    (net (code "81") (name "Net-(R2-Pad1)") (class "Default")
      (node (ref "R2") (pin "1") (pinfunction "1_1") (pintype "passive"))
      (node (ref "RESET") (pin "1") (pintype "passive"))
    )
    (net (code "82") (name "Net-(SRF04-ECHO)") (class "Default")
      (node (ref "JP10") (pin "1") (pinfunction "1_1") (pintype "passive"))
      (node (ref "SRF04") (pin "2") (pinfunction "ECHO_2") (pintype "passive"))
    )
    (net (code "83") (name "Net-(SRF04-TRIG)") (class "Default")
      (node (ref "JP9") (pin "1") (pinfunction "1_1") (pintype "passive"))
      (node (ref "SRF04") (pin "3") (pinfunction "TRIG_3") (pintype "passive"))
    )
    (net (code "84") (name "Net-(U0-C1+)") (class "Default")
      (node (ref "C9") (pin "1") (pinfunction "1_1") (pintype "passive"))
      (node (ref "U0") (pin "1") (pinfunction "C1+_1") (pintype "passive"))
    )
    (net (code "85") (name "Net-(U0-C1-)") (class "Default")
      (node (ref "C9") (pin "2") (pinfunction "2_2") (pintype "passive"))
      (node (ref "U0") (pin "3") (pinfunction "C1-_3") (pintype "passive"))
    )
    (net (code "86") (name "Net-(U0-C2+)") (class "Default")
      (node (ref "C8") (pin "1") (pinfunction "1_1") (pintype "passive"))
      (node (ref "U0") (pin "4") (pinfunction "C2+_4") (pintype "passive"))
    )
    (net (code "87") (name "Net-(U0-C2-)") (class "Default")
      (node (ref "C8") (pin "2") (pinfunction "2_2") (pintype "passive"))
      (node (ref "U0") (pin "5") (pinfunction "C2-_5") (pintype "passive"))
    )
    (net (code "88") (name "Net-(U0-VS+)") (class "Default")
      (node (ref "C7") (pin "1") (pinfunction "1_1") (pintype "passive"))
      (node (ref "U0") (pin "2") (pinfunction "VS+_2") (pintype "power_in"))
    )
    (net (code "89") (name "Net-(U0-VS-)") (class "Default")
      (node (ref "C6") (pin "2") (pinfunction "2_2") (pintype "passive"))
      (node (ref "U0") (pin "6") (pinfunction "VS-_6") (pintype "power_in"))
    )
    (net (code "90") (name "unconnected-(D-Sub-MH1-Pad10)") (class "Default")
      (node (ref "D-Sub") (pin "10") (pinfunction "MH1_10") (pintype "passive"))
    )
    (net (code "91") (name "unconnected-(D-Sub-MH2-Pad11)") (class "Default")
      (node (ref "D-Sub") (pin "11") (pinfunction "MH2_11") (pintype "passive"))
    )
    (net (code "92") (name "unconnected-(D-Sub-Pad1)") (class "Default")
      (node (ref "D-Sub") (pin "1") (pinfunction "1_1") (pintype "passive"))
    )
    (net (code "93") (name "unconnected-(D-Sub-Pad4)") (class "Default")
      (node (ref "D-Sub") (pin "4") (pinfunction "4_4") (pintype "passive"))
    )
    (net (code "94") (name "unconnected-(D-Sub-Pad6)") (class "Default")
      (node (ref "D-Sub") (pin "6") (pinfunction "6_6") (pintype "passive"))
    )
    (net (code "95") (name "unconnected-(D-Sub-Pad7)") (class "Default")
      (node (ref "D-Sub") (pin "7") (pinfunction "7_7") (pintype "passive"))
    )
    (net (code "96") (name "unconnected-(D-Sub-Pad8)") (class "Default")
      (node (ref "D-Sub") (pin "8") (pinfunction "8_8") (pintype "passive"))
    )
    (net (code "97") (name "unconnected-(D-Sub-Pad9)") (class "Default")
      (node (ref "D-Sub") (pin "9") (pinfunction "9_9") (pintype "passive"))
    )
    (net (code "98") (name "unconnected-(ICSP-Pad6)") (class "Default")
      (node (ref "ICSP") (pin "6") (pinfunction "6_6") (pintype "passive+no_connect"))
    )
    (net (code "99") (name "unconnected-(J28-Pad2)") (class "Default")
      (node (ref "J28") (pin "2") (pinfunction "2_2") (pintype "passive"))
    )
    (net (code "100") (name "unconnected-(J28-Pad4)") (class "Default")
      (node (ref "J28") (pin "4") (pinfunction "4_4") (pintype "passive"))
    )
    (net (code "101") (name "unconnected-(JDC-S-Pad3)") (class "Default")
      (node (ref "JDC") (pin "3") (pinfunction "S_3") (pintype "power_in"))
    )
    (net (code "102") (name "unconnected-(RB0-Pad3)") (class "Default")
      (node (ref "RB0") (pin "3") (pinfunction "3_3") (pintype "passive"))
    )
    (net (code "103") (name "unconnected-(RB0-Pad4)") (class "Default")
      (node (ref "RB0") (pin "4") (pinfunction "4_4") (pintype "passive"))
    )
    (net (code "104") (name "unconnected-(RB1-Pad3)") (class "Default")
      (node (ref "RB1") (pin "3") (pinfunction "3_3") (pintype "passive"))
    )
    (net (code "105") (name "unconnected-(RB1-Pad4)") (class "Default")
      (node (ref "RB1") (pin "4") (pinfunction "4_4") (pintype "passive"))
    )
    (net (code "106") (name "unconnected-(RB2-Pad3)") (class "Default")
      (node (ref "RB2") (pin "3") (pinfunction "3_3") (pintype "passive"))
    )
    (net (code "107") (name "unconnected-(RB2-Pad4)") (class "Default")
      (node (ref "RB2") (pin "4") (pinfunction "4_4") (pintype "passive"))
    )
    (net (code "108") (name "unconnected-(RB3-Pad3)") (class "Default")
      (node (ref "RB3") (pin "3") (pinfunction "3_3") (pintype "passive"))
    )
    (net (code "109") (name "unconnected-(RB3-Pad4)") (class "Default")
      (node (ref "RB3") (pin "4") (pinfunction "4_4") (pintype "passive"))
    )
    (net (code "110") (name "unconnected-(RB4-Pad3)") (class "Default")
      (node (ref "RB4") (pin "3") (pinfunction "3_3") (pintype "passive"))
    )
    (net (code "111") (name "unconnected-(RB4-Pad4)") (class "Default")
      (node (ref "RB4") (pin "4") (pinfunction "4_4") (pintype "passive"))
    )
    (net (code "112") (name "unconnected-(RB5-Pad3)") (class "Default")
      (node (ref "RB5") (pin "3") (pinfunction "3_3") (pintype "passive"))
    )
    (net (code "113") (name "unconnected-(RB5-Pad4)") (class "Default")
      (node (ref "RB5") (pin "4") (pinfunction "4_4") (pintype "passive"))
    )
    (net (code "114") (name "unconnected-(RESET-Pad3)") (class "Default")
      (node (ref "RESET") (pin "3") (pinfunction "3_3") (pintype "passive"))
    )
    (net (code "115") (name "unconnected-(RESET-Pad4)") (class "Default")
      (node (ref "RESET") (pin "4") (pinfunction "4_4") (pintype "passive"))
    )
    (net (code "116") (name "unconnected-(U0-R2IN-Pad8)") (class "Default")
      (node (ref "U0") (pin "8") (pinfunction "R2IN_8") (pintype "input+no_connect"))
    )
    (net (code "117") (name "unconnected-(U0-R2~{OUT}-Pad9)") (class "Default")
      (node (ref "U0") (pin "9") (pinfunction "R2~{OUT}_9") (pintype "output+no_connect"))
    )
    (net (code "118") (name "unconnected-(U0-T2IN-Pad10)") (class "Default")
      (node (ref "U0") (pin "10") (pinfunction "T2IN_10") (pintype "input+no_connect"))
    )
    (net (code "119") (name "unconnected-(U0-T2~{OUT}-Pad7)") (class "Default")
      (node (ref "U0") (pin "7") (pinfunction "T2~{OUT}_7") (pintype "output+no_connect"))
    )
    (net (code "120") (name "unconnected-(VR0-Pad1)") (class "Default")
      (node (ref "VR0") (pin "1") (pinfunction "1_1") (pintype "passive+no_connect"))
    )
    (net (code "121") (name "unconnected-(VR0-Pad2)") (class "Default")
      (node (ref "VR0") (pin "2") (pinfunction "2_2") (pintype "passive+no_connect"))
    )
    (net (code "122") (name "unconnected-(VR0-Pad3)") (class "Default")
      (node (ref "VR0") (pin "3") (pinfunction "3_3") (pintype "passive+no_connect"))
    )
  )
)
